# knock_lock.net
KiCad netlist of a schematic drawn in EAGLE
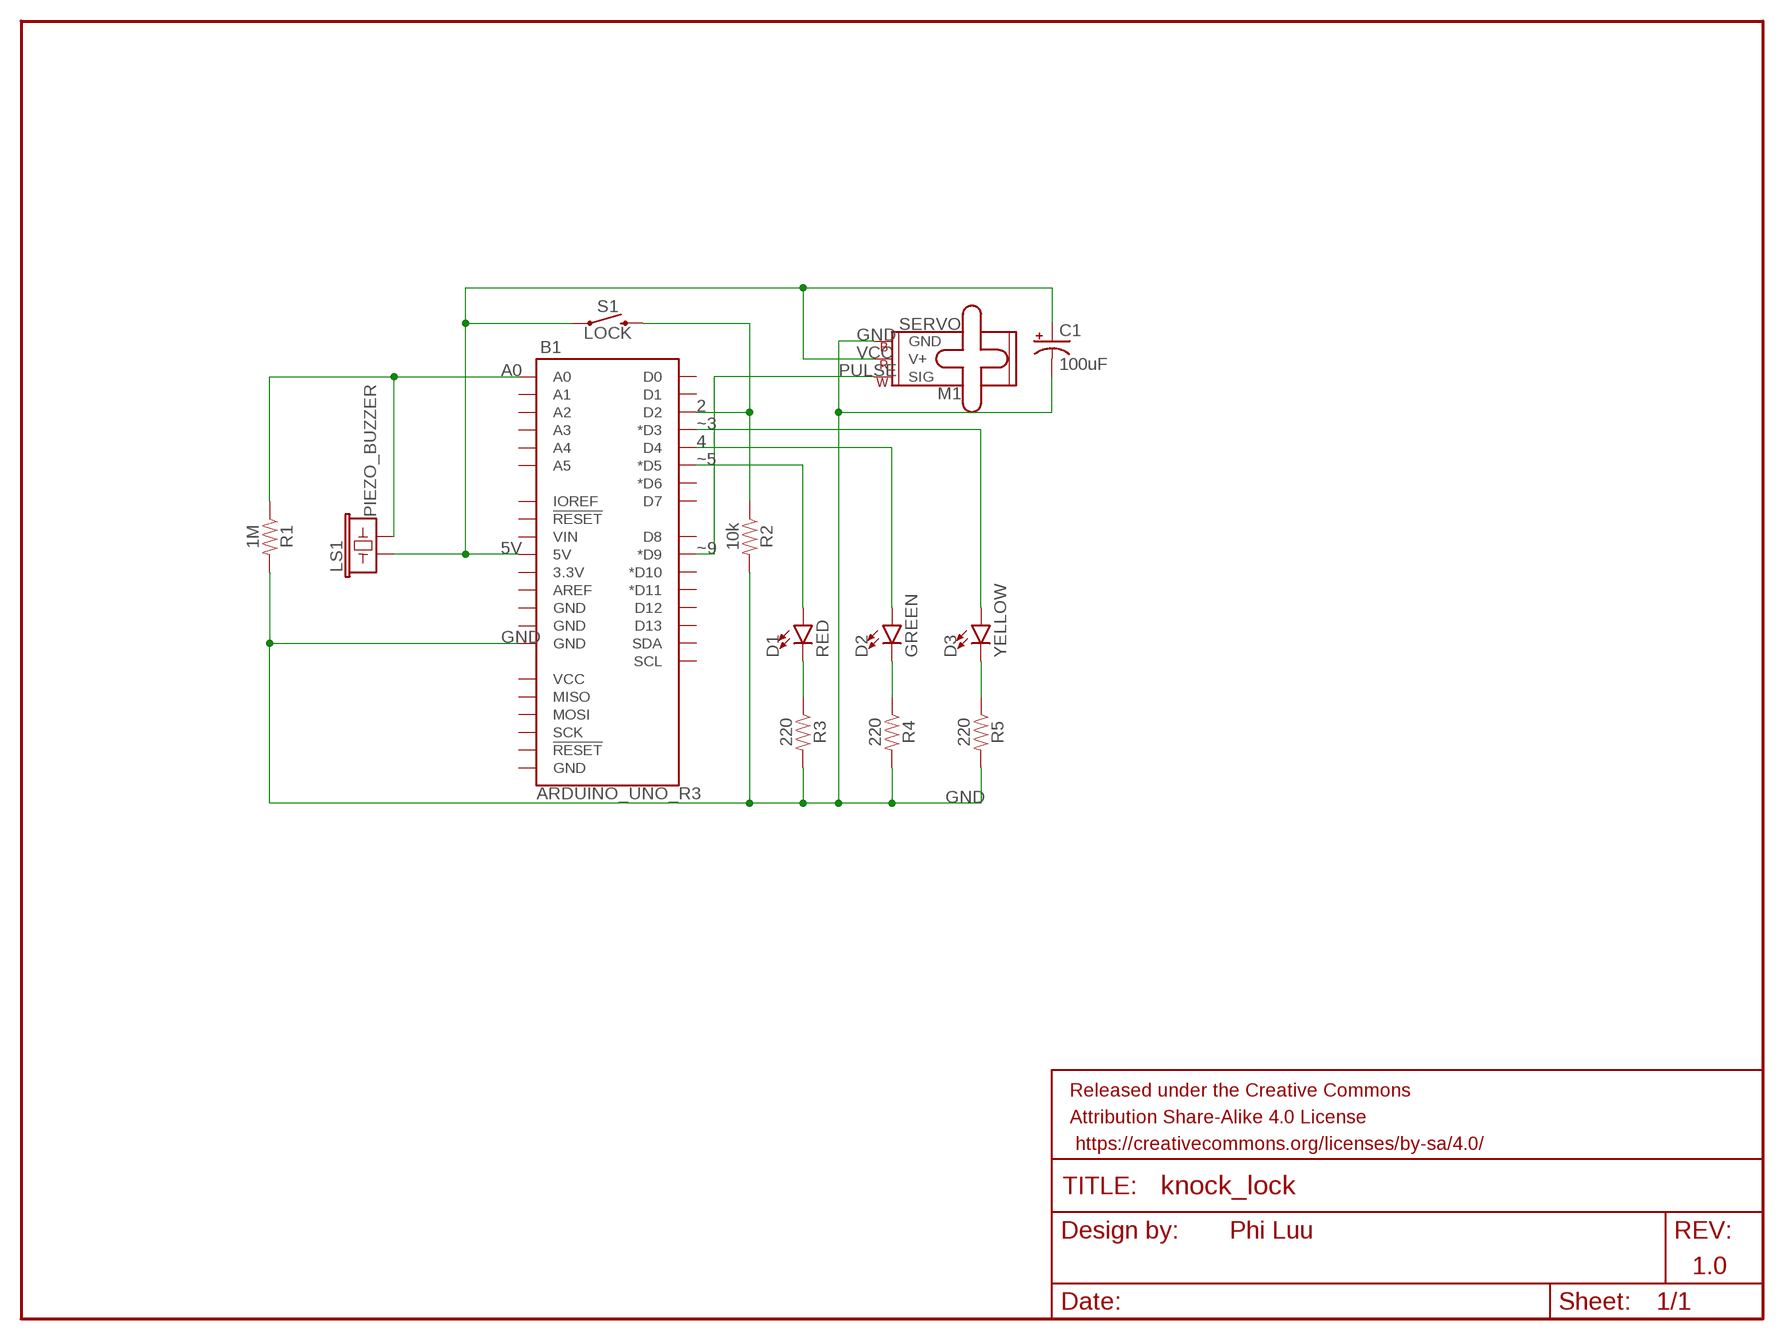
[diagram p0: schematic, sheet 1]

(export (version "E")
  (design (tool "Eeschema 10.0.6"))
  (components
    (comp (ref "B1")
      (value "ARDUINO_UNO_R3")
      (footprint "eagle-import:ARDUINO_R3")
      (libsource (lib "eagle-import") (part "ARDUINO_UNO_R3"))
    )
    (comp (ref "C1")
      (value "100uF")
      (footprint "eagle-import:CPOL-RADIAL-2.5MM-6.5MM")
      (libsource (lib "eagle-import") (part "100UF-POLAR-RADIAL-2.5MM-25V-20%"))
    )
    (comp (ref "D1")
      (value "RED")
      (footprint "eagle-import:LED_5MM")
      (libsource (lib "eagle-import") (part "LED5MM"))
    )
    (comp (ref "D2")
      (value "GREEN")
      (footprint "eagle-import:LED_5MM")
      (libsource (lib "eagle-import") (part "LED5MM"))
    )
    (comp (ref "D3")
      (value "YELLOW")
      (footprint "eagle-import:LED_5MM")
      (libsource (lib "eagle-import") (part "LED5MM"))
    )
    (comp (ref "FRAME1")
      (value "FRAME-LETTER")
      (footprint "eagle-import:CREATIVE_COMMONS")
      (libsource (lib "eagle-import") (part "FRAME-LETTER"))
    )
    (comp (ref "LS1")
      (value "PIEZO_BUZZER")
      (footprint "eagle-import:BUZZER-12MM")
      (libsource (lib "eagle-import") (part "BUZZER-PTH"))
    )
    (comp (ref "M1")
      (value "SERVO")
      (footprint "eagle-import:1X03")
      (libsource (lib "eagle-import") (part "SERVO"))
    )
    (comp (ref "R1")
      (value "1M")
      (footprint "eagle-import:AXIAL-0.3")
      (libsource (lib "eagle-import") (part "1MOHM-HORIZ-1/4W-5%"))
    )
    (comp (ref "R2")
      (value "10k")
      (footprint "eagle-import:AXIAL-0.3")
      (libsource (lib "eagle-import") (part "10KOHM-HORIZ-1/4W-5%"))
    )
    (comp (ref "R3")
      (value "220")
      (footprint "eagle-import:AXIAL-0.3")
      (libsource (lib "eagle-import") (part "10KOHM-HORIZ-1/4W-5%"))
    )
    (comp (ref "R4")
      (value "220")
      (footprint "eagle-import:AXIAL-0.3")
      (libsource (lib "eagle-import") (part "10KOHM-HORIZ-1/4W-5%"))
    )
    (comp (ref "R5")
      (value "220")
      (footprint "eagle-import:AXIAL-0.3")
      (libsource (lib "eagle-import") (part "10KOHM-HORIZ-1/4W-5%"))
    )
    (comp (ref "S1")
      (value "LOCK")
      (footprint "eagle-import:TACTILE_SWITCH_PTH_6.0MM")
      (libsource (lib "eagle-import") (part "MOMENTARY-SWITCH-SPST-PTH-6.0MM"))
    )
  )
  (nets
    (net (code "1") (name "/2") (class "Default")
      (node (ref "B1") (pin "D2") (pinfunction "D2_D2") (pintype "bidirectional"))
      (node (ref "R2") (pin "P$1") (pinfunction "1_P$1") (pintype "passive"))
      (node (ref "S1") (pin "3") (pinfunction "2_3") (pintype "passive"))
    )
    (net (code "2") (name "/4") (class "Default")
      (node (ref "B1") (pin "D4") (pinfunction "D4_D4") (pintype "bidirectional"))
      (node (ref "D2") (pin "A") (pinfunction "A_A") (pintype "passive"))
    )
    (net (code "3") (name "/5V") (class "Default")
      (node (ref "B1") (pin "5V") (pinfunction "5V_5V") (pintype "bidirectional"))
      (node (ref "C1") (pin "1") (pinfunction "+_1") (pintype "passive"))
      (node (ref "LS1") (pin "+") (pinfunction "1_+") (pintype "passive"))
      (node (ref "M1") (pin "2") (pinfunction "V+_2") (pintype "bidirectional"))
      (node (ref "S1") (pin "1") (pinfunction "1_1") (pintype "passive"))
    )
    (net (code "4") (name "/A0") (class "Default")
      (node (ref "B1") (pin "A0") (pinfunction "A0_A0") (pintype "bidirectional"))
      (node (ref "LS1") (pin "-") (pinfunction "2_-") (pintype "passive"))
      (node (ref "R1") (pin "P$1") (pinfunction "1_P$1") (pintype "passive"))
    )
    (net (code "5") (name "/GND") (class "Default")
      (node (ref "B1") (pin "GND@2") (pinfunction "GND_GND@2") (pintype "bidirectional"))
      (node (ref "C1") (pin "2") (pinfunction "-_2") (pintype "passive"))
      (node (ref "M1") (pin "3") (pinfunction "GND_3") (pintype "bidirectional"))
      (node (ref "R1") (pin "P$2") (pinfunction "2_P$2") (pintype "passive"))
      (node (ref "R2") (pin "P$2") (pinfunction "2_P$2") (pintype "passive"))
      (node (ref "R3") (pin "P$2") (pinfunction "2_P$2") (pintype "passive"))
      (node (ref "R4") (pin "P$2") (pinfunction "2_P$2") (pintype "passive"))
      (node (ref "R5") (pin "P$2") (pinfunction "2_P$2") (pintype "passive"))
    )
    (net (code "6") (name "/~{3}") (class "Default")
      (node (ref "B1") (pin "D3") (pinfunction "*D3_D3") (pintype "bidirectional"))
      (node (ref "D3") (pin "A") (pinfunction "A_A") (pintype "passive"))
    )
    (net (code "7") (name "/~{5}") (class "Default")
      (node (ref "B1") (pin "D5") (pinfunction "*D5_D5") (pintype "bidirectional"))
      (node (ref "D1") (pin "A") (pinfunction "A_A") (pintype "passive"))
    )
    (net (code "8") (name "/~{9}") (class "Default")
      (node (ref "B1") (pin "D9") (pinfunction "*D9_D9") (pintype "bidirectional"))
      (node (ref "M1") (pin "1") (pinfunction "SIG_1") (pintype "bidirectional"))
    )
    (net (code "9") (name "Net-(D1-C)") (class "Default")
      (node (ref "D1") (pin "K") (pinfunction "C_K") (pintype "passive"))
      (node (ref "R3") (pin "P$1") (pinfunction "1_P$1") (pintype "passive"))
    )
    (net (code "10") (name "Net-(D2-C)") (class "Default")
      (node (ref "D2") (pin "K") (pinfunction "C_K") (pintype "passive"))
      (node (ref "R4") (pin "P$1") (pinfunction "1_P$1") (pintype "passive"))
    )
    (net (code "11") (name "Net-(D3-C)") (class "Default")
      (node (ref "D3") (pin "K") (pinfunction "C_K") (pintype "passive"))
      (node (ref "R5") (pin "P$1") (pinfunction "1_P$1") (pintype "passive"))
    )
    (net (code "12") (name "unconnected-(B1-*D6-PadD6)") (class "Default")
      (node (ref "B1") (pin "D6") (pinfunction "*D6_D6") (pintype "bidirectional"))
    )
    (net (code "13") (name "unconnected-(B1-*D10-PadD10)") (class "Default")
      (node (ref "B1") (pin "D10") (pinfunction "*D10_D10") (pintype "bidirectional"))
    )
    (net (code "14") (name "unconnected-(B1-*D11-PadD11)") (class "Default")
      (node (ref "B1") (pin "D11") (pinfunction "*D11_D11") (pintype "bidirectional"))
    )
    (net (code "15") (name "unconnected-(B1-GND-PadGND@1)") (class "Default")
      (node (ref "B1") (pin "GND@1") (pinfunction "GND_GND@1") (pintype "bidirectional"))
    )
    (net (code "16") (name "unconnected-(B1-GND-PadGND@3)") (class "Default")
      (node (ref "B1") (pin "GND@3") (pinfunction "GND_GND@3") (pintype "bidirectional"))
    )
    (net (code "17") (name "unconnected-(B1-GND-PadGND@4)") (class "Default")
      (node (ref "B1") (pin "GND@4") (pinfunction "GND_GND@4") (pintype "bidirectional"))
    )
    (net (code "18") (name "unconnected-(B1-Pad3.3V)") (class "Default")
      (node (ref "B1") (pin "3.3V") (pinfunction "3.3V_3.3V") (pintype "bidirectional"))
    )
    (net (code "19") (name "unconnected-(B1-PadA1)") (class "Default")
      (node (ref "B1") (pin "A1") (pinfunction "A1_A1") (pintype "bidirectional"))
    )
    (net (code "20") (name "unconnected-(B1-PadA2)") (class "Default")
      (node (ref "B1") (pin "A2") (pinfunction "A2_A2") (pintype "bidirectional"))
    )
    (net (code "21") (name "unconnected-(B1-PadA3)") (class "Default")
      (node (ref "B1") (pin "A3") (pinfunction "A3_A3") (pintype "bidirectional"))
    )
    (net (code "22") (name "unconnected-(B1-PadA4)") (class "Default")
      (node (ref "B1") (pin "A4") (pinfunction "A4_A4") (pintype "bidirectional"))
    )
    (net (code "23") (name "unconnected-(B1-PadA5)") (class "Default")
      (node (ref "B1") (pin "A5") (pinfunction "A5_A5") (pintype "bidirectional"))
    )
    (net (code "24") (name "unconnected-(B1-PadAREF)") (class "Default")
      (node (ref "B1") (pin "AREF") (pinfunction "AREF_AREF") (pintype "bidirectional"))
    )
    (net (code "25") (name "unconnected-(B1-PadD0)") (class "Default")
      (node (ref "B1") (pin "D0") (pinfunction "D0_D0") (pintype "bidirectional"))
    )
    (net (code "26") (name "unconnected-(B1-PadD1)") (class "Default")
      (node (ref "B1") (pin "D1") (pinfunction "D1_D1") (pintype "bidirectional"))
    )
    (net (code "27") (name "unconnected-(B1-PadD7)") (class "Default")
      (node (ref "B1") (pin "D7") (pinfunction "D7_D7") (pintype "bidirectional"))
    )
    (net (code "28") (name "unconnected-(B1-PadD8)") (class "Default")
      (node (ref "B1") (pin "D8") (pinfunction "D8_D8") (pintype "bidirectional"))
    )
    (net (code "29") (name "unconnected-(B1-PadD12)") (class "Default")
      (node (ref "B1") (pin "D12") (pinfunction "D12_D12") (pintype "bidirectional"))
    )
    (net (code "30") (name "unconnected-(B1-PadD13)") (class "Default")
      (node (ref "B1") (pin "D13") (pinfunction "D13_D13") (pintype "bidirectional"))
    )
    (net (code "31") (name "unconnected-(B1-PadIOREF)") (class "Default")
      (node (ref "B1") (pin "IOREF") (pinfunction "IOREF_IOREF") (pintype "bidirectional"))
    )
    (net (code "32") (name "unconnected-(B1-PadMISO)") (class "Default")
      (node (ref "B1") (pin "MISO") (pinfunction "MISO_MISO") (pintype "bidirectional"))
    )
    (net (code "33") (name "unconnected-(B1-PadMOSI)") (class "Default")
      (node (ref "B1") (pin "MOSI") (pinfunction "MOSI_MOSI") (pintype "bidirectional"))
    )
    (net (code "34") (name "unconnected-(B1-PadSCK)") (class "Default")
      (node (ref "B1") (pin "SCK") (pinfunction "SCK_SCK") (pintype "bidirectional"))
    )
    (net (code "35") (name "unconnected-(B1-PadSCL)") (class "Default")
      (node (ref "B1") (pin "SCL") (pinfunction "SCL_SCL") (pintype "bidirectional"))
    )
    (net (code "36") (name "unconnected-(B1-PadSDA)") (class "Default")
      (node (ref "B1") (pin "SDA") (pinfunction "SDA_SDA") (pintype "bidirectional"))
    )
    (net (code "37") (name "unconnected-(B1-PadVCC)") (class "Default")
      (node (ref "B1") (pin "VCC") (pinfunction "VCC_VCC") (pintype "bidirectional"))
    )
    (net (code "38") (name "unconnected-(B1-PadVIN)") (class "Default")
      (node (ref "B1") (pin "VIN") (pinfunction "VIN_VIN") (pintype "bidirectional"))
    )
    (net (code "39") (name "unconnected-(B1-~{RESET}-PadRESET@1)") (class "Default")
      (node (ref "B1") (pin "RESET@1") (pinfunction "~{RESET}_RESET@1") (pintype "bidirectional"))
    )
    (net (code "40") (name "unconnected-(B1-~{RESET}-PadRESET@2)") (class "Default")
      (node (ref "B1") (pin "RESET@2") (pinfunction "~{RESET}_RESET@2") (pintype "bidirectional"))
    )
  )
)
